# 1_USB_HUB.net
KiCad netlist of a schematic drawn in Altium Designer
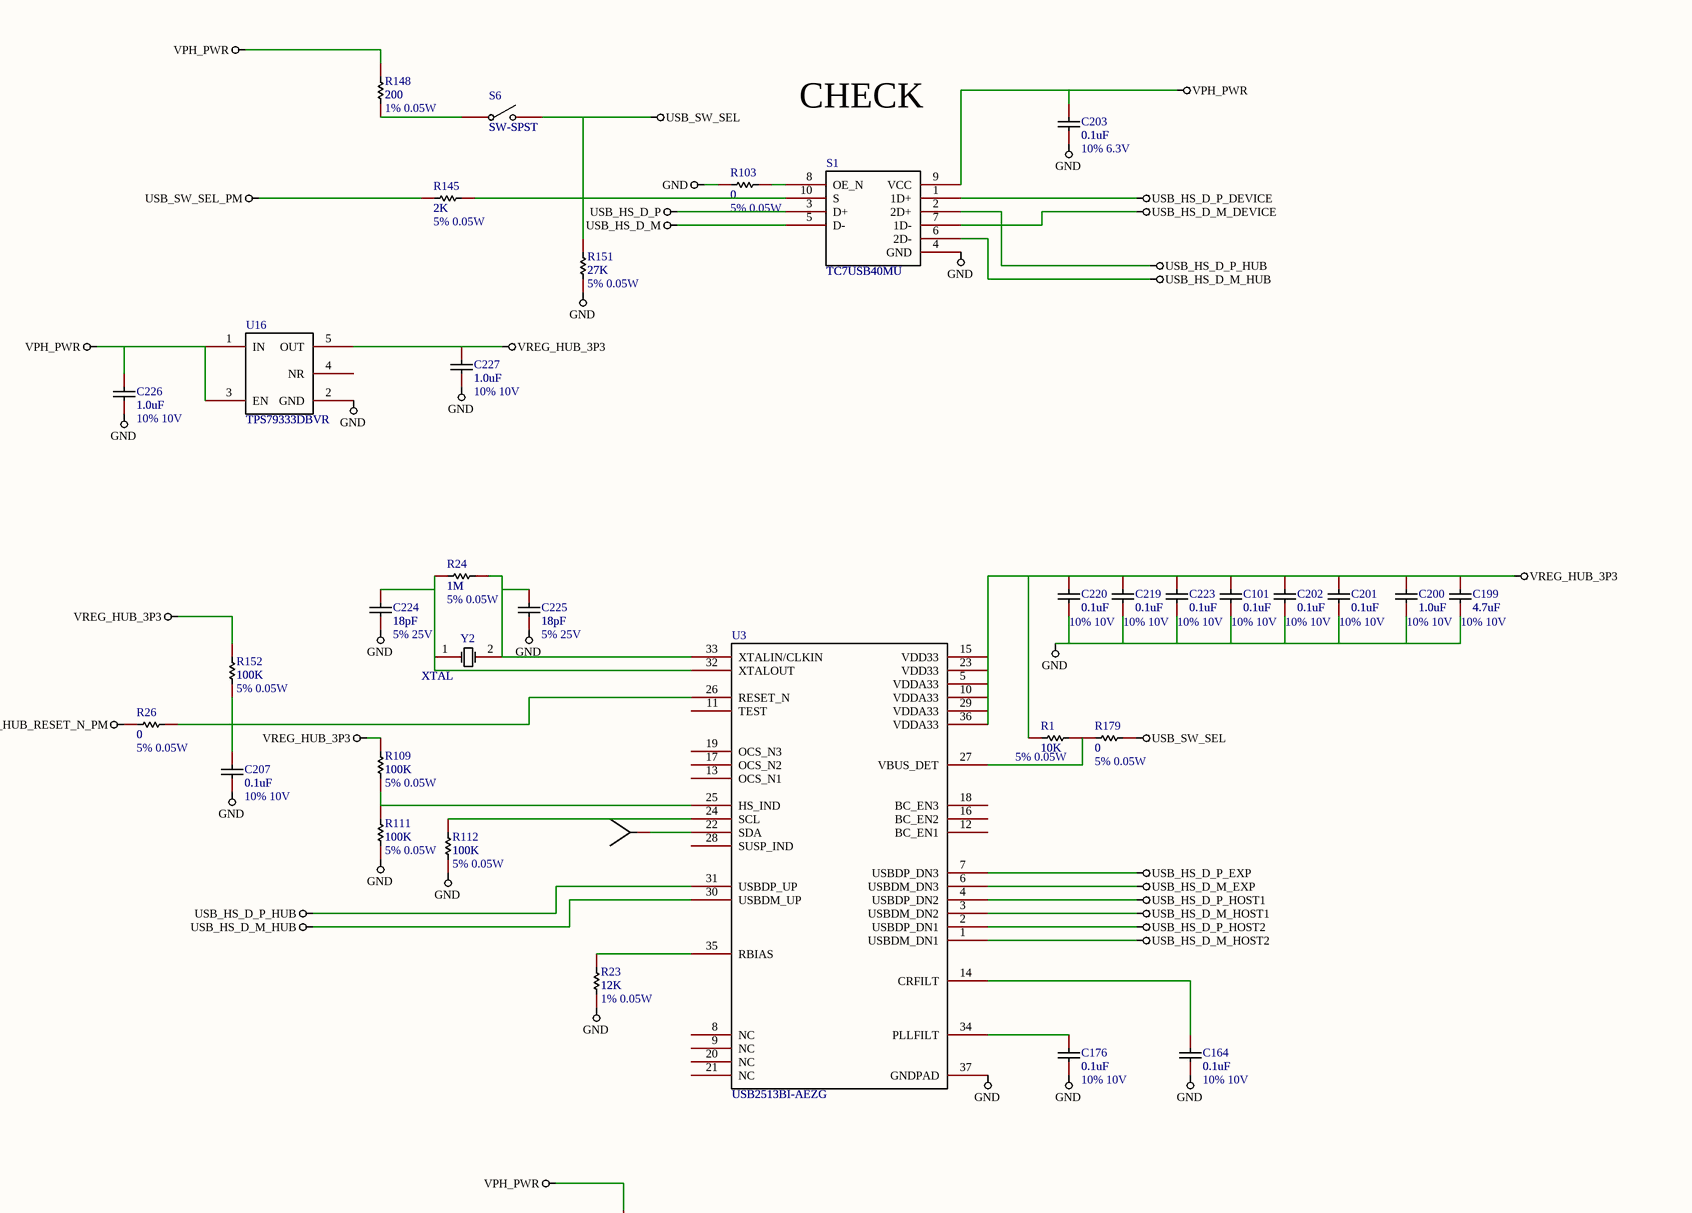
[diagram p0: 1_USB_HUB.schdoc, top left]
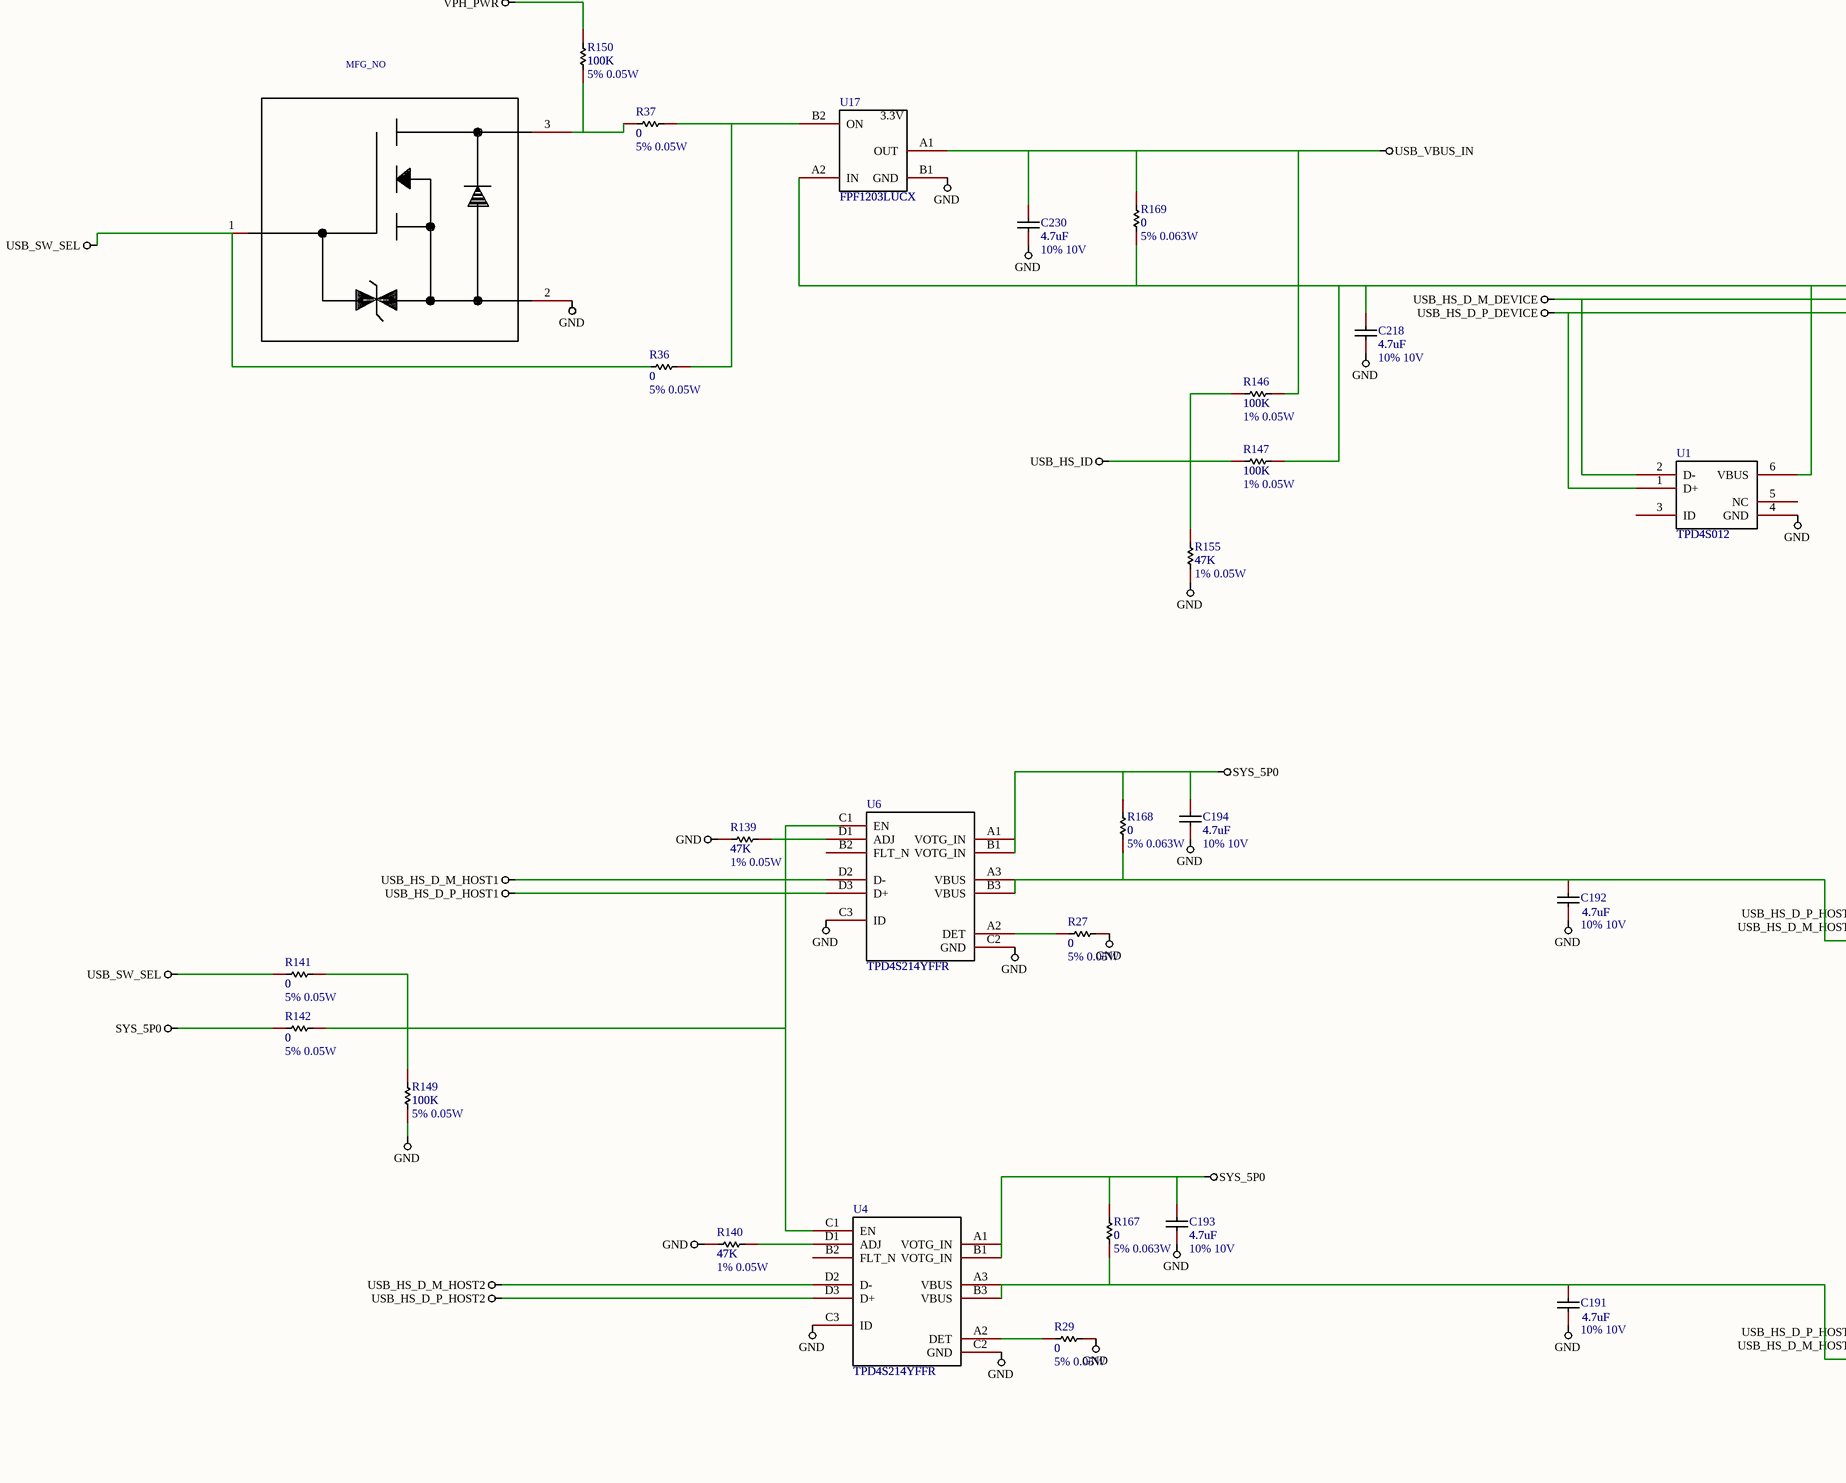
[diagram p1: 1_USB_HUB.schdoc, bottom left]
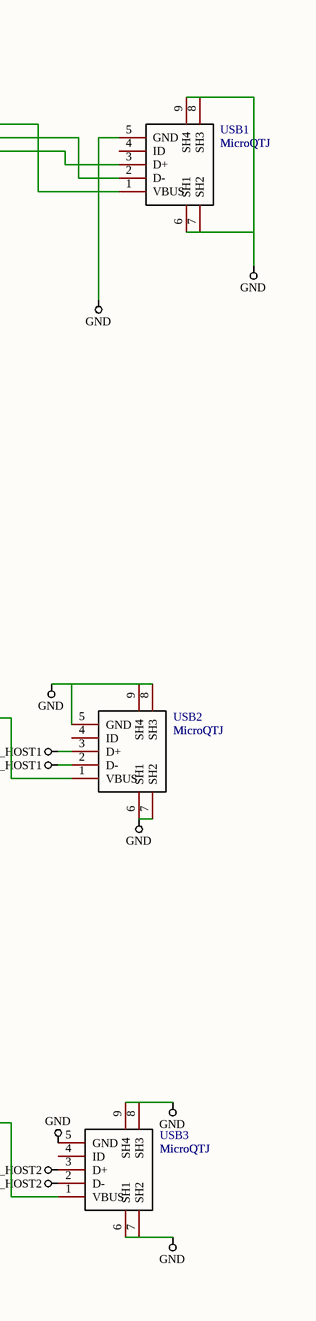
[diagram p2: 1_USB_HUB.schdoc, bottom right]

(export (version "E")
  (design (tool "Eeschema 10.0.6"))
  (components
    (comp (ref "C101")
      (value "0.1uF")
      (description "Capacitor")
      (fields
        (field (name "NAME") "0.1uF")
        (field (name "ALTIUM_VALUE") "10% 10V")
        (field (name "PUBLISHER") "Altium Limited")
      )
      (libsource (lib "altium-import") (part "root_1_0.1uF_"))
    )
    (comp (ref "C164")
      (value "0.1uF")
      (description "Capacitor")
      (fields
        (field (name "NAME") "0.1uF")
        (field (name "ALTIUM_VALUE") "10% 10V")
        (field (name "PUBLISHER") "Altium Limited")
      )
      (libsource (lib "altium-import") (part "root_1_0.1uF_"))
    )
    (comp (ref "C176")
      (value "0.1uF")
      (description "Capacitor")
      (fields
        (field (name "NAME") "0.1uF")
        (field (name "ALTIUM_VALUE") "10% 10V")
        (field (name "PUBLISHER") "Altium Limited")
      )
      (libsource (lib "altium-import") (part "root_1_0.1uF_"))
    )
    (comp (ref "C191")
      (value "4.7uF")
      (description "Capacitor")
      (fields
        (field (name "NAME") "4.7uF")
        (field (name "ALTIUM_VALUE") "10% 10V")
        (field (name "PUBLISHER") "Altium Limited")
      )
      (libsource (lib "altium-import") (part "root_3_4.7uF_"))
    )
    (comp (ref "C192")
      (value "4.7uF")
      (description "Capacitor")
      (fields
        (field (name "NAME") "4.7uF")
        (field (name "ALTIUM_VALUE") "10% 10V")
        (field (name "PUBLISHER") "Altium Limited")
      )
      (libsource (lib "altium-import") (part "root_3_4.7uF_"))
    )
    (comp (ref "C193")
      (value "4.7uF")
      (description "Capacitor")
      (fields
        (field (name "NAME") "4.7uF")
        (field (name "ALTIUM_VALUE") "10% 10V")
        (field (name "PUBLISHER") "Altium Limited")
      )
      (libsource (lib "altium-import") (part "root_1_4.7uF_"))
    )
    (comp (ref "C194")
      (value "4.7uF")
      (description "Capacitor")
      (fields
        (field (name "NAME") "4.7uF")
        (field (name "ALTIUM_VALUE") "10% 10V")
        (field (name "PUBLISHER") "Altium Limited")
      )
      (libsource (lib "altium-import") (part "root_1_4.7uF_"))
    )
    (comp (ref "C199")
      (value "4.7uF")
      (description "Capacitor")
      (fields
        (field (name "NAME") "4.7uF")
        (field (name "ALTIUM_VALUE") "10% 10V")
        (field (name "PUBLISHER") "Altium Limited")
      )
      (libsource (lib "altium-import") (part "root_1_4.7uF_"))
    )
    (comp (ref "C200")
      (value "1.0uF")
      (description "Capacitor")
      (fields
        (field (name "NAME") "1.0uF")
        (field (name "ALTIUM_VALUE") "10% 10V")
        (field (name "PUBLISHER") "Altium Limited")
      )
      (libsource (lib "altium-import") (part "root_1_1.0uF_"))
    )
    (comp (ref "C201")
      (value "0.1uF")
      (description "Capacitor")
      (fields
        (field (name "NAME") "0.1uF")
        (field (name "ALTIUM_VALUE") "10% 10V")
        (field (name "PUBLISHER") "Altium Limited")
      )
      (libsource (lib "altium-import") (part "root_1_0.1uF_"))
    )
    (comp (ref "C202")
      (value "0.1uF")
      (description "Capacitor")
      (fields
        (field (name "NAME") "0.1uF")
        (field (name "ALTIUM_VALUE") "10% 10V")
        (field (name "PUBLISHER") "Altium Limited")
      )
      (libsource (lib "altium-import") (part "root_1_0.1uF_"))
    )
    (comp (ref "C203")
      (value "0.1uF")
      (description "Capacitor")
      (fields
        (field (name "NAME") "0.1uF")
        (field (name "ALTIUM_VALUE") "10% 6.3V")
        (field (name "PUBLISHER") "Altium Limited")
      )
      (libsource (lib "altium-import") (part "root_3_0.1uF_"))
    )
    (comp (ref "C207")
      (value "0.1uF")
      (description "Capacitor")
      (fields
        (field (name "NAME") "0.1uF")
        (field (name "ALTIUM_VALUE") "10% 10V")
        (field (name "PUBLISHER") "Altium Limited")
      )
      (libsource (lib "altium-import") (part "root_1_0.1uF_"))
    )
    (comp (ref "C218")
      (value "4.7uF")
      (description "Capacitor")
      (fields
        (field (name "NAME") "4.7uF")
        (field (name "ALTIUM_VALUE") "10% 10V")
        (field (name "PUBLISHER") "Altium Limited")
      )
      (libsource (lib "altium-import") (part "root_1_4.7uF_"))
    )
    (comp (ref "C219")
      (value "0.1uF")
      (description "Capacitor")
      (fields
        (field (name "NAME") "0.1uF")
        (field (name "ALTIUM_VALUE") "10% 10V")
        (field (name "PUBLISHER") "Altium Limited")
      )
      (libsource (lib "altium-import") (part "root_1_0.1uF_"))
    )
    (comp (ref "C220")
      (value "0.1uF")
      (description "Capacitor")
      (fields
        (field (name "NAME") "0.1uF")
        (field (name "ALTIUM_VALUE") "10% 10V")
        (field (name "PUBLISHER") "Altium Limited")
      )
      (libsource (lib "altium-import") (part "root_1_0.1uF_"))
    )
    (comp (ref "C223")
      (value "0.1uF")
      (description "Capacitor")
      (fields
        (field (name "NAME") "0.1uF")
        (field (name "ALTIUM_VALUE") "10% 10V")
        (field (name "PUBLISHER") "Altium Limited")
      )
      (libsource (lib "altium-import") (part "root_1_0.1uF_"))
    )
    (comp (ref "C224")
      (value "18pF")
      (description "Capacitor")
      (fields
        (field (name "NAME") "18pF")
        (field (name "ALTIUM_VALUE") "5% 25V")
        (field (name "PUBLISHER") "Altium Limited")
      )
      (libsource (lib "altium-import") (part "root_1_18pF_"))
    )
    (comp (ref "C225")
      (value "18pF")
      (description "Capacitor")
      (fields
        (field (name "NAME") "18pF")
        (field (name "ALTIUM_VALUE") "5% 25V")
        (field (name "PUBLISHER") "Altium Limited")
      )
      (libsource (lib "altium-import") (part "root_1_18pF_"))
    )
    (comp (ref "C226")
      (value "1.0uF")
      (description "Capacitor")
      (fields
        (field (name "NAME") "1.0uF")
        (field (name "ALTIUM_VALUE") "10% 10V")
        (field (name "PUBLISHER") "Altium Limited")
      )
      (libsource (lib "altium-import") (part "root_1_1.0uF_"))
    )
    (comp (ref "C227")
      (value "1.0uF")
      (description "Capacitor")
      (fields
        (field (name "NAME") "1.0uF")
        (field (name "ALTIUM_VALUE") "10% 10V")
        (field (name "PUBLISHER") "Altium Limited")
      )
      (libsource (lib "altium-import") (part "root_1_1.0uF_"))
    )
    (comp (ref "C230")
      (value "4.7uF")
      (description "Capacitor")
      (fields
        (field (name "NAME") "4.7uF")
        (field (name "ALTIUM_VALUE") "10% 10V")
        (field (name "PUBLISHER") "Altium Limited")
      )
      (libsource (lib "altium-import") (part "root_1_4.7uF_"))
    )
    (comp (ref "Q1")
      (value "nfet_zener_bidir")
      (fields
        (field (name "PART_NUMBER") "MCN_NO")
        (field (name "PART_ID") "MFG_NO")
        (field (name "LIBRARY NAME") "MSM8916_DRAM_PMIC_REF_Library")
      )
      (libsource (lib "altium-import") (part "root_0_nfet_zener_bidir_"))
    )
    (comp (ref "R1")
      (value "10K")
      (description "Resistor")
      (fields
        (field (name "NAME") "10K")
        (field (name "ALTIUM_VALUE") "5% 0.05W")
        (field (name "PUBLISHER") "Altium Limited")
      )
      (libsource (lib "altium-import") (part "root_2_10K_"))
    )
    (comp (ref "R23")
      (value "12K")
      (description "Resistor")
      (fields
        (field (name "NAME") "12K")
        (field (name "ALTIUM_VALUE") "1% 0.05W")
        (field (name "PUBLISHER") "Altium Limited")
      )
      (libsource (lib "altium-import") (part "root_1_12K_"))
    )
    (comp (ref "R24")
      (value "1M")
      (description "Resistor")
      (fields
        (field (name "NAME") "1M")
        (field (name "ALTIUM_VALUE") "5% 0.05W")
        (field (name "PUBLISHER") "Altium Limited")
      )
      (libsource (lib "altium-import") (part "root_0_1M_"))
    )
    (comp (ref "R26")
      (value "0")
      (description "Resistor")
      (fields
        (field (name "NAME") "0")
        (field (name "ALTIUM_VALUE") "5% 0.05W")
        (field (name "PUBLISHER") "Altium Limited")
      )
      (libsource (lib "altium-import") (part "root_0_0_"))
    )
    (comp (ref "R27")
      (value "0")
      (description "Resistor")
      (fields
        (field (name "NAME") "0")
        (field (name "ALTIUM_VALUE") "5% 0.05W")
        (field (name "PUBLISHER") "Altium Limited")
      )
      (libsource (lib "altium-import") (part "root_0_0_"))
    )
    (comp (ref "R29")
      (value "0")
      (description "Resistor")
      (fields
        (field (name "NAME") "0")
        (field (name "ALTIUM_VALUE") "5% 0.05W")
        (field (name "PUBLISHER") "Altium Limited")
      )
      (libsource (lib "altium-import") (part "root_0_0_"))
    )
    (comp (ref "R36")
      (value "0")
      (description "Resistor")
      (fields
        (field (name "NAME") "0")
        (field (name "ALTIUM_VALUE") "5% 0.05W")
        (field (name "PUBLISHER") "Altium Limited")
      )
      (libsource (lib "altium-import") (part "root_0_0_"))
    )
    (comp (ref "R37")
      (value "0")
      (description "Resistor")
      (fields
        (field (name "NAME") "0")
        (field (name "ALTIUM_VALUE") "5% 0.05W")
        (field (name "PUBLISHER") "Altium Limited")
      )
      (libsource (lib "altium-import") (part "root_0_0_"))
    )
    (comp (ref "R103")
      (value "0")
      (description "Resistor")
      (fields
        (field (name "NAME") "0")
        (field (name "ALTIUM_VALUE") "5% 0.05W")
        (field (name "PUBLISHER") "Altium Limited")
      )
      (libsource (lib "altium-import") (part "root_0_0_"))
    )
    (comp (ref "R109")
      (value "100K")
      (description "Resistor")
      (fields
        (field (name "NAME") "100K")
        (field (name "ALTIUM_VALUE") "5% 0.05W")
        (field (name "PUBLISHER") "Altium Limited")
      )
      (libsource (lib "altium-import") (part "root_1_100K_"))
    )
    (comp (ref "R111")
      (value "100K")
      (description "Resistor")
      (fields
        (field (name "NAME") "100K")
        (field (name "ALTIUM_VALUE") "5% 0.05W")
        (field (name "PUBLISHER") "Altium Limited")
      )
      (libsource (lib "altium-import") (part "root_1_100K_"))
    )
    (comp (ref "R112")
      (value "100K")
      (description "Resistor")
      (fields
        (field (name "NAME") "100K")
        (field (name "ALTIUM_VALUE") "5% 0.05W")
        (field (name "PUBLISHER") "Altium Limited")
      )
      (libsource (lib "altium-import") (part "root_1_100K_"))
    )
    (comp (ref "R139")
      (value "47K")
      (description "Resistor")
      (fields
        (field (name "NAME") "47K")
        (field (name "ALTIUM_VALUE") "1% 0.05W")
        (field (name "PUBLISHER") "Altium Limited")
      )
      (libsource (lib "altium-import") (part "root_0_47K_"))
    )
    (comp (ref "R140")
      (value "47K")
      (description "Resistor")
      (fields
        (field (name "NAME") "47K")
        (field (name "ALTIUM_VALUE") "1% 0.05W")
        (field (name "PUBLISHER") "Altium Limited")
      )
      (libsource (lib "altium-import") (part "root_0_47K_"))
    )
    (comp (ref "R141")
      (value "0")
      (description "Resistor")
      (fields
        (field (name "NAME") "0")
        (field (name "ALTIUM_VALUE") "5% 0.05W")
        (field (name "PUBLISHER") "Altium Limited")
      )
      (libsource (lib "altium-import") (part "root_0_0_"))
    )
    (comp (ref "R142")
      (value "0")
      (description "Resistor")
      (fields
        (field (name "NAME") "0")
        (field (name "ALTIUM_VALUE") "5% 0.05W")
        (field (name "PUBLISHER") "Altium Limited")
      )
      (libsource (lib "altium-import") (part "root_0_0_"))
    )
    (comp (ref "R145")
      (value "2K")
      (description "Resistor")
      (fields
        (field (name "NAME") "2K")
        (field (name "ALTIUM_VALUE") "5% 0.05W")
        (field (name "PUBLISHER") "Altium Limited")
      )
      (libsource (lib "altium-import") (part "root_0_2K_"))
    )
    (comp (ref "R146")
      (value "100K")
      (description "Resistor")
      (fields
        (field (name "NAME") "100K")
        (field (name "ALTIUM_VALUE") "1% 0.05W")
        (field (name "PUBLISHER") "Altium Limited")
      )
      (libsource (lib "altium-import") (part "root_0_100K_"))
    )
    (comp (ref "R147")
      (value "100K")
      (description "Resistor")
      (fields
        (field (name "NAME") "100K")
        (field (name "ALTIUM_VALUE") "1% 0.05W")
        (field (name "PUBLISHER") "Altium Limited")
      )
      (libsource (lib "altium-import") (part "root_0_100K_"))
    )
    (comp (ref "R148")
      (value "200")
      (description "Resistor")
      (fields
        (field (name "NAME") "200")
        (field (name "ALTIUM_VALUE") "1% 0.05W")
        (field (name "PUBLISHER") "Altium Limited")
      )
      (libsource (lib "altium-import") (part "root_1_200_"))
    )
    (comp (ref "R149")
      (value "100K")
      (description "Resistor")
      (fields
        (field (name "NAME") "100K")
        (field (name "ALTIUM_VALUE") "5% 0.05W")
        (field (name "PUBLISHER") "Altium Limited")
      )
      (libsource (lib "altium-import") (part "root_1_100K_"))
    )
    (comp (ref "R150")
      (value "100K")
      (description "Resistor")
      (fields
        (field (name "NAME") "100K")
        (field (name "ALTIUM_VALUE") "5% 0.05W")
        (field (name "PUBLISHER") "Altium Limited")
      )
      (libsource (lib "altium-import") (part "root_1_100K_"))
    )
    (comp (ref "R151")
      (value "27K")
      (description "Resistor")
      (fields
        (field (name "NAME") "27K")
        (field (name "ALTIUM_VALUE") "5% 0.05W")
        (field (name "PUBLISHER") "Altium Limited")
      )
      (libsource (lib "altium-import") (part "root_1_27K_"))
    )
    (comp (ref "R152")
      (value "100K")
      (description "Resistor")
      (fields
        (field (name "NAME") "100K")
        (field (name "ALTIUM_VALUE") "5% 0.05W")
        (field (name "PUBLISHER") "Altium Limited")
      )
      (libsource (lib "altium-import") (part "root_1_100K_"))
    )
    (comp (ref "R155")
      (value "47K")
      (description "Resistor")
      (fields
        (field (name "NAME") "47K")
        (field (name "ALTIUM_VALUE") "1% 0.05W")
        (field (name "PUBLISHER") "Altium Limited")
      )
      (libsource (lib "altium-import") (part "root_1_47K_"))
    )
    (comp (ref "R167")
      (value "0")
      (description "Resistor")
      (fields
        (field (name "NAME") "0")
        (field (name "ALTIUM_VALUE") "5% 0.063W")
        (field (name "PUBLISHER") "Altium Limited")
      )
      (libsource (lib "altium-import") (part "root_1_0_"))
    )
    (comp (ref "R168")
      (value "0")
      (description "Resistor")
      (fields
        (field (name "NAME") "0")
        (field (name "ALTIUM_VALUE") "5% 0.063W")
        (field (name "PUBLISHER") "Altium Limited")
      )
      (libsource (lib "altium-import") (part "root_1_0_"))
    )
    (comp (ref "R169")
      (value "0")
      (description "Resistor")
      (fields
        (field (name "NAME") "0")
        (field (name "ALTIUM_VALUE") "5% 0.063W")
        (field (name "PUBLISHER") "Altium Limited")
      )
      (libsource (lib "altium-import") (part "root_1_0_"))
    )
    (comp (ref "R179")
      (value "0")
      (description "Resistor")
      (fields
        (field (name "NAME") "0")
        (field (name "ALTIUM_VALUE") "5% 0.05W")
        (field (name "PUBLISHER") "Altium Limited")
      )
      (libsource (lib "altium-import") (part "root_2_0_"))
    )
    (comp (ref "S1")
      (value "TC7USB40MU")
      (fields
        (field (name "NAME") "TC7USB40MU")
        (field (name "LIBRARY NAME") "MSM8916_DRAM_PMIC_REF_Library")
      )
      (libsource (lib "altium-import") (part "root_0_TC7USB40MU_"))
    )
    (comp (ref "S6")
      (value "SW-SPST")
      (description "Single-Pole, Single-Throw Switch")
      (fields (field (name "NAME") "SW-SPST") (field (name "PUBLISHER") "Altium Limited"))
      (libsource (lib "altium-import") (part "root_0_SW-SPST_"))
    )
    (comp (ref "TP18")
      (value "TP")
      (fields
        (field (name "PART_NUMBER") "MCN_NO")
        (field (name "LIBRARY NAME") "MSM8916_DRAM_PMIC_REF_Library")
      )
      (libsource (lib "altium-import") (part "root_1_TP_"))
    )
    (comp (ref "U1")
      (value "TPD4S012")
      (fields (field (name "NAME") "TPD4S012") (field (name "LIBRARY NAME") "MSM8916_DRAM_PMIC_REF_Library"))
      (libsource (lib "altium-import") (part "root_0_TPD4S012_"))
    )
    (comp (ref "U3")
      (value "USB2513BI-AEZG")
      (fields
        (field (name "NAME") "USB2513BI-AEZG")
        (field (name "LIBRARY NAME") "MSM8916_DRAM_PMIC_REF_Library")
      )
      (libsource (lib "altium-import") (part "root_0_USB2513BI-AEZG_"))
    )
    (comp (ref "U4")
      (value "TPD4S214YFFR")
      (fields
        (field (name "NAME") "TPD4S214YFFR")
        (field (name "LIBRARY NAME") "MSM8916_DRAM_PMIC_REF_Library")
      )
      (libsource (lib "altium-import") (part "root_0_TPD4S214YFFR_"))
    )
    (comp (ref "U6")
      (value "TPD4S214YFFR")
      (fields
        (field (name "NAME") "TPD4S214YFFR")
        (field (name "LIBRARY NAME") "MSM8916_DRAM_PMIC_REF_Library")
      )
      (libsource (lib "altium-import") (part "root_0_TPD4S214YFFR_"))
    )
    (comp (ref "U16")
      (value "TPS79333DBVR")
      (fields
        (field (name "NAME") "TPS79333DBVR")
        (field (name "LIBRARY NAME") "MSM8916_DRAM_PMIC_REF_Library")
      )
      (libsource (lib "altium-import") (part "root_0_TPS79333DBVR_"))
    )
    (comp (ref "U17")
      (value "FPF1203LUCX")
      (fields
        (field (name "NAME") "FPF1203LUCX")
        (field (name "LIBRARY NAME") "MSM8916_DRAM_PMIC_REF_Library")
      )
      (libsource (lib "altium-import") (part "root_0_FPF1203LUCX_"))
    )
    (comp (ref "USB1")
      (value "MicroQTJ")
      (description "连接器类型:Micro-B;标准:USB 2.0;公母:母座;触点数量:5;端口数量:1;安装方式:卧贴;额定电流 - 电源:-;工作温度范围:-30℃~+80℃;")
      (fields (field (name "NAME") "MicroQTJ") (field (name "MANUFACTURER") "SHOU HAN(首韩)"))
      (libsource (lib "altium-import") (part "root_2_MicroQTJ_"))
    )
    (comp (ref "USB2")
      (value "MicroQTJ")
      (description "连接器类型:Micro-B;标准:USB 2.0;公母:母座;触点数量:5;端口数量:1;安装方式:卧贴;额定电流 - 电源:-;工作温度范围:-30℃~+80℃;")
      (fields (field (name "NAME") "MicroQTJ") (field (name "MANUFACTURER") "SHOU HAN(首韩)"))
      (libsource (lib "altium-import") (part "root_2_MicroQTJ_"))
    )
    (comp (ref "USB3")
      (value "MicroQTJ")
      (description "连接器类型:Micro-B;标准:USB 2.0;公母:母座;触点数量:5;端口数量:1;安装方式:卧贴;额定电流 - 电源:-;工作温度范围:-30℃~+80℃;")
      (fields (field (name "NAME") "MicroQTJ") (field (name "MANUFACTURER") "SHOU HAN(首韩)"))
      (libsource (lib "altium-import") (part "root_2_MicroQTJ_"))
    )
    (comp (ref "Y2")
      (value "XTAL")
      (description "Crystal Oscillator")
      (fields (field (name "NAME") "XTAL") (field (name "PUBLISHER") "Altium Limited"))
      (libsource (lib "altium-import") (part "root_0_XTAL_"))
    )
  )
  (nets
    (net (code "1") (name "GND") (class "Default")
      (node (ref "C101") (pin "1") (pinfunction "1_1") (pintype "passive"))
      (node (ref "C164") (pin "1") (pinfunction "1_1") (pintype "passive"))
      (node (ref "C176") (pin "1") (pinfunction "1_1") (pintype "passive"))
      (node (ref "C191") (pin "2") (pinfunction "2_2") (pintype "passive"))
      (node (ref "C192") (pin "2") (pinfunction "2_2") (pintype "passive"))
      (node (ref "C193") (pin "1") (pinfunction "1_1") (pintype "passive"))
      (node (ref "C194") (pin "1") (pinfunction "1_1") (pintype "passive"))
      (node (ref "C199") (pin "1") (pinfunction "1_1") (pintype "passive"))
      (node (ref "C200") (pin "1") (pinfunction "1_1") (pintype "passive"))
      (node (ref "C201") (pin "1") (pinfunction "1_1") (pintype "passive"))
      (node (ref "C202") (pin "1") (pinfunction "1_1") (pintype "passive"))
      (node (ref "C203") (pin "2") (pinfunction "2_2") (pintype "passive"))
      (node (ref "C207") (pin "1") (pinfunction "1_1") (pintype "passive"))
      (node (ref "C218") (pin "1") (pinfunction "1_1") (pintype "passive"))
      (node (ref "C219") (pin "1") (pinfunction "1_1") (pintype "passive"))
      (node (ref "C220") (pin "1") (pinfunction "1_1") (pintype "passive"))
      (node (ref "C223") (pin "1") (pinfunction "1_1") (pintype "passive"))
      (node (ref "C224") (pin "1") (pinfunction "1_1") (pintype "passive"))
      (node (ref "C225") (pin "1") (pinfunction "1_1") (pintype "passive"))
      (node (ref "C226") (pin "1") (pinfunction "1_1") (pintype "passive"))
      (node (ref "C227") (pin "1") (pinfunction "1_1") (pintype "passive"))
      (node (ref "C230") (pin "1") (pinfunction "1_1") (pintype "passive"))
      (node (ref "Q1") (pin "2") (pinfunction "S_2") (pintype "passive"))
      (node (ref "R103") (pin "1") (pinfunction "1_1") (pintype "passive"))
      (node (ref "R111") (pin "1") (pinfunction "1_1") (pintype "passive"))
      (node (ref "R112") (pin "1") (pinfunction "1_1") (pintype "passive"))
      (node (ref "R139") (pin "1") (pinfunction "1_1") (pintype "passive"))
      (node (ref "R140") (pin "1") (pinfunction "1_1") (pintype "passive"))
      (node (ref "R149") (pin "1") (pinfunction "1_1") (pintype "passive"))
      (node (ref "R151") (pin "1") (pinfunction "1_1") (pintype "passive"))
      (node (ref "R155") (pin "1") (pinfunction "1_1") (pintype "passive"))
      (node (ref "R23") (pin "1") (pinfunction "1_1") (pintype "passive"))
      (node (ref "R27") (pin "2") (pinfunction "2_2") (pintype "passive"))
      (node (ref "R29") (pin "2") (pinfunction "2_2") (pintype "passive"))
      (node (ref "S1") (pin "4") (pinfunction "GND_4") (pintype "passive"))
      (node (ref "U1") (pin "4") (pinfunction "GND_4") (pintype "passive"))
      (node (ref "U16") (pin "2") (pinfunction "GND_2") (pintype "passive"))
      (node (ref "U17") (pin "B1") (pinfunction "GND_B1") (pintype "passive"))
      (node (ref "U3") (pin "37") (pinfunction "GNDPAD_37") (pintype "passive"))
      (node (ref "U4") (pin "C2") (pinfunction "GND_C2") (pintype "passive"))
      (node (ref "U4") (pin "C3") (pinfunction "ID_C3") (pintype "passive"))
      (node (ref "U6") (pin "C2") (pinfunction "GND_C2") (pintype "passive"))
      (node (ref "U6") (pin "C3") (pinfunction "ID_C3") (pintype "passive"))
      (node (ref "USB1") (pin "5") (pinfunction "GND_5") (pintype "passive"))
      (node (ref "USB1") (pin "6") (pinfunction "SH1_6") (pintype "passive"))
      (node (ref "USB1") (pin "7") (pinfunction "SH2_7") (pintype "passive"))
      (node (ref "USB1") (pin "8") (pinfunction "SH3_8") (pintype "passive"))
      (node (ref "USB1") (pin "9") (pinfunction "SH4_9") (pintype "passive"))
      (node (ref "USB2") (pin "5") (pinfunction "GND_5") (pintype "passive"))
      (node (ref "USB2") (pin "6") (pinfunction "SH1_6") (pintype "passive"))
      (node (ref "USB2") (pin "7") (pinfunction "SH2_7") (pintype "passive"))
      (node (ref "USB2") (pin "8") (pinfunction "SH3_8") (pintype "passive"))
      (node (ref "USB2") (pin "9") (pinfunction "SH4_9") (pintype "passive"))
      (node (ref "USB3") (pin "5") (pinfunction "GND_5") (pintype "passive"))
      (node (ref "USB3") (pin "6") (pinfunction "SH1_6") (pintype "passive"))
      (node (ref "USB3") (pin "7") (pinfunction "SH2_7") (pintype "passive"))
      (node (ref "USB3") (pin "8") (pinfunction "SH3_8") (pintype "passive"))
      (node (ref "USB3") (pin "9") (pinfunction "SH4_9") (pintype "passive"))
    )
    (net (code "2") (name "Net-(Q1-D)") (class "Default")
      (node (ref "Q1") (pin "3") (pinfunction "D_3") (pintype "passive"))
      (node (ref "R150") (pin "1") (pinfunction "1_1") (pintype "passive"))
      (node (ref "R37") (pin "1") (pinfunction "1_1") (pintype "passive"))
    )
    (net (code "3") (name "Net-(S1-OE_N)") (class "Default")
      (node (ref "R103") (pin "2") (pinfunction "2_2") (pintype "passive"))
      (node (ref "S1") (pin "8") (pinfunction "OE_N_8") (pintype "passive"))
    )
    (net (code "4") (name "Net-(S6-COMMON)") (class "Default")
      (node (ref "R148") (pin "1") (pinfunction "1_1") (pintype "passive"))
      (node (ref "S6") (pin "1") (pinfunction "COMMON_1") (pintype "passive"))
    )
    (net (code "5") (name "Net-(TP18-IO1)") (class "Default")
      (node (ref "TP18") (pin "1") (pinfunction "IO1_1") (pintype "passive"))
      (node (ref "U3") (pin "22") (pinfunction "SDA_22") (pintype "passive"))
    )
    (net (code "6") (name "Net-(U1-VBUS)") (class "Default")
      (node (ref "C218") (pin "2") (pinfunction "2_2") (pintype "passive"))
      (node (ref "R147") (pin "2") (pinfunction "2_2") (pintype "passive"))
      (node (ref "R169") (pin "1") (pinfunction "1_1") (pintype "passive"))
      (node (ref "U1") (pin "6") (pinfunction "VBUS_6") (pintype "passive"))
      (node (ref "U17") (pin "A2") (pinfunction "IN_A2") (pintype "passive"))
      (node (ref "USB1") (pin "1") (pinfunction "VBUS_1") (pintype "passive"))
    )
    (net (code "7") (name "Net-(U3-CRFILT)") (class "Default")
      (node (ref "C164") (pin "2") (pinfunction "2_2") (pintype "passive"))
      (node (ref "U3") (pin "14") (pinfunction "CRFILT_14") (pintype "passive"))
    )
    (net (code "8") (name "Net-(U3-HS_IND)") (class "Default")
      (node (ref "R109") (pin "1") (pinfunction "1_1") (pintype "passive"))
      (node (ref "R111") (pin "2") (pinfunction "2_2") (pintype "passive"))
      (node (ref "U3") (pin "25") (pinfunction "HS_IND_25") (pintype "passive"))
    )
    (net (code "9") (name "Net-(U3-PLLFILT)") (class "Default")
      (node (ref "C176") (pin "2") (pinfunction "2_2") (pintype "passive"))
      (node (ref "U3") (pin "34") (pinfunction "PLLFILT_34") (pintype "passive"))
    )
    (net (code "10") (name "Net-(U3-RBIAS)") (class "Default")
      (node (ref "R23") (pin "2") (pinfunction "2_2") (pintype "passive"))
      (node (ref "U3") (pin "35") (pinfunction "RBIAS_35") (pintype "passive"))
    )
    (net (code "11") (name "Net-(U3-RESET_N)") (class "Default")
      (node (ref "C207") (pin "2") (pinfunction "2_2") (pintype "passive"))
      (node (ref "R152") (pin "1") (pinfunction "1_1") (pintype "passive"))
      (node (ref "R26") (pin "2") (pinfunction "2_2") (pintype "passive"))
      (node (ref "U3") (pin "26") (pinfunction "RESET_N_26") (pintype "passive"))
    )
    (net (code "12") (name "Net-(U3-SCL)") (class "Default")
      (node (ref "R112") (pin "2") (pinfunction "2_2") (pintype "passive"))
      (node (ref "U3") (pin "24") (pinfunction "SCL_24") (pintype "passive"))
    )
    (net (code "13") (name "Net-(U3-VBUS_DET)") (class "Default")
      (node (ref "R1") (pin "1") (pinfunction "1_1") (pintype "passive"))
      (node (ref "R179") (pin "2") (pinfunction "2_2") (pintype "passive"))
      (node (ref "U3") (pin "27") (pinfunction "VBUS_DET_27") (pintype "passive"))
    )
    (net (code "14") (name "Net-(U3-XTALIN{slash}CLKIN)") (class "Default")
      (node (ref "C225") (pin "2") (pinfunction "2_2") (pintype "passive"))
      (node (ref "R24") (pin "2") (pinfunction "2_2") (pintype "passive"))
      (node (ref "U3") (pin "33") (pinfunction "XTALIN/CLKIN_33") (pintype "passive"))
      (node (ref "Y2") (pin "2") (pinfunction "OSC2_2") (pintype "passive"))
    )
    (net (code "15") (name "Net-(U3-XTALOUT)") (class "Default")
      (node (ref "C224") (pin "2") (pinfunction "2_2") (pintype "passive"))
      (node (ref "R24") (pin "1") (pinfunction "1_1") (pintype "passive"))
      (node (ref "U3") (pin "32") (pinfunction "XTALOUT_32") (pintype "passive"))
      (node (ref "Y2") (pin "1") (pinfunction "OSC1_1") (pintype "passive"))
    )
    (net (code "16") (name "Net-(U4-ADJ)") (class "Default")
      (node (ref "R140") (pin "2") (pinfunction "2_2") (pintype "passive"))
      (node (ref "U4") (pin "D1") (pinfunction "ADJ_D1") (pintype "passive"))
    )
    (net (code "17") (name "Net-(U4-DET)") (class "Default")
      (node (ref "R29") (pin "1") (pinfunction "1_1") (pintype "passive"))
      (node (ref "U4") (pin "A2") (pinfunction "DET_A2") (pintype "passive"))
    )
    (net (code "18") (name "Net-(U4-EN)") (class "Default")
      (node (ref "R141") (pin "2") (pinfunction "2_2") (pintype "passive"))
      (node (ref "R142") (pin "2") (pinfunction "2_2") (pintype "passive"))
      (node (ref "R149") (pin "2") (pinfunction "2_2") (pintype "passive"))
      (node (ref "U4") (pin "C1") (pinfunction "EN_C1") (pintype "passive"))
      (node (ref "U6") (pin "C1") (pinfunction "EN_C1") (pintype "passive"))
    )
    (net (code "19") (name "Net-(U6-ADJ)") (class "Default")
      (node (ref "R139") (pin "2") (pinfunction "2_2") (pintype "passive"))
      (node (ref "U6") (pin "D1") (pinfunction "ADJ_D1") (pintype "passive"))
    )
    (net (code "20") (name "Net-(U6-DET)") (class "Default")
      (node (ref "R27") (pin "1") (pinfunction "1_1") (pintype "passive"))
      (node (ref "U6") (pin "A2") (pinfunction "DET_A2") (pintype "passive"))
    )
    (net (code "21") (name "Net-(U17-ON)") (class "Default")
      (node (ref "R36") (pin "2") (pinfunction "2_2") (pintype "passive"))
      (node (ref "R37") (pin "2") (pinfunction "2_2") (pintype "passive"))
      (node (ref "U17") (pin "B2") (pinfunction "ON_B2") (pintype "passive"))
    )
    (net (code "22") (name "Net-(USB2-VBUS)") (class "Default")
      (node (ref "C192") (pin "1") (pinfunction "1_1") (pintype "passive"))
      (node (ref "R168") (pin "1") (pinfunction "1_1") (pintype "passive"))
      (node (ref "U6") (pin "A3") (pinfunction "VBUS_A3") (pintype "passive"))
      (node (ref "U6") (pin "B3") (pinfunction "VBUS_B3") (pintype "passive"))
      (node (ref "USB2") (pin "1") (pinfunction "VBUS_1") (pintype "passive"))
    )
    (net (code "23") (name "Net-(USB3-VBUS)") (class "Default")
      (node (ref "C191") (pin "1") (pinfunction "1_1") (pintype "passive"))
      (node (ref "R167") (pin "1") (pinfunction "1_1") (pintype "passive"))
      (node (ref "U4") (pin "A3") (pinfunction "VBUS_A3") (pintype "passive"))
      (node (ref "U4") (pin "B3") (pinfunction "VBUS_B3") (pintype "passive"))
      (node (ref "USB3") (pin "1") (pinfunction "VBUS_1") (pintype "passive"))
    )
    (net (code "24") (name "SYS_5P0") (class "Default")
      (node (ref "C193") (pin "2") (pinfunction "2_2") (pintype "passive"))
      (node (ref "C194") (pin "2") (pinfunction "2_2") (pintype "passive"))
      (node (ref "R142") (pin "1") (pinfunction "1_1") (pintype "passive"))
      (node (ref "R167") (pin "2") (pinfunction "2_2") (pintype "passive"))
      (node (ref "R168") (pin "2") (pinfunction "2_2") (pintype "passive"))
      (node (ref "U4") (pin "A1") (pinfunction "VOTG_IN_A1") (pintype "passive"))
      (node (ref "U4") (pin "B1") (pinfunction "VOTG_IN_B1") (pintype "passive"))
      (node (ref "U6") (pin "A1") (pinfunction "VOTG_IN_A1") (pintype "passive"))
      (node (ref "U6") (pin "B1") (pinfunction "VOTG_IN_B1") (pintype "passive"))
    )
    (net (code "25") (name "USB_HS_D_M") (class "Default")
      (node (ref "S1") (pin "5") (pinfunction "D-_5") (pintype "passive"))
    )
    (net (code "26") (name "USB_HS_D_M_DEVICE") (class "Default")
      (node (ref "S1") (pin "7") (pinfunction "1D-_7") (pintype "passive"))
      (node (ref "U1") (pin "2") (pinfunction "D-_2") (pintype "passive"))
      (node (ref "USB1") (pin "2") (pinfunction "D-_2") (pintype "passive"))
    )
    (net (code "27") (name "USB_HS_D_M_EXP") (class "Default")
      (node (ref "U3") (pin "6") (pinfunction "USBDM_DN3_6") (pintype "passive"))
    )
    (net (code "28") (name "USB_HS_D_M_HOST1") (class "Default")
      (node (ref "U3") (pin "3") (pinfunction "USBDM_DN2_3") (pintype "passive"))
      (node (ref "U6") (pin "D2") (pinfunction "D-_D2") (pintype "passive"))
      (node (ref "USB2") (pin "2") (pinfunction "D-_2") (pintype "passive"))
    )
    (net (code "29") (name "USB_HS_D_M_HOST2") (class "Default")
      (node (ref "U3") (pin "1") (pinfunction "USBDM_DN1_1") (pintype "passive"))
      (node (ref "U4") (pin "D2") (pinfunction "D-_D2") (pintype "passive"))
      (node (ref "USB3") (pin "2") (pinfunction "D-_2") (pintype "passive"))
    )
    (net (code "30") (name "USB_HS_D_M_HUB") (class "Default")
      (node (ref "S1") (pin "6") (pinfunction "2D-_6") (pintype "passive"))
      (node (ref "U3") (pin "30") (pinfunction "USBDM_UP_30") (pintype "passive"))
    )
    (net (code "31") (name "USB_HS_D_P") (class "Default")
      (node (ref "S1") (pin "3") (pinfunction "D+_3") (pintype "passive"))
    )
    (net (code "32") (name "USB_HS_D_P_DEVICE") (class "Default")
      (node (ref "S1") (pin "1") (pinfunction "1D+_1") (pintype "passive"))
      (node (ref "U1") (pin "1") (pinfunction "D+_1") (pintype "passive"))
      (node (ref "USB1") (pin "3") (pinfunction "D+_3") (pintype "passive"))
    )
    (net (code "33") (name "USB_HS_D_P_EXP") (class "Default")
      (node (ref "U3") (pin "7") (pinfunction "USBDP_DN3_7") (pintype "passive"))
    )
    (net (code "34") (name "USB_HS_D_P_HOST1") (class "Default")
      (node (ref "U3") (pin "4") (pinfunction "USBDP_DN2_4") (pintype "passive"))
      (node (ref "U6") (pin "D3") (pinfunction "D+_D3") (pintype "passive"))
      (node (ref "USB2") (pin "3") (pinfunction "D+_3") (pintype "passive"))
    )
    (net (code "35") (name "USB_HS_D_P_HOST2") (class "Default")
      (node (ref "U3") (pin "2") (pinfunction "USBDP_DN1_2") (pintype "passive"))
      (node (ref "U4") (pin "D3") (pinfunction "D+_D3") (pintype "passive"))
      (node (ref "USB3") (pin "3") (pinfunction "D+_3") (pintype "passive"))
    )
    (net (code "36") (name "USB_HS_D_P_HUB") (class "Default")
      (node (ref "S1") (pin "2") (pinfunction "2D+_2") (pintype "passive"))
      (node (ref "U3") (pin "31") (pinfunction "USBDP_UP_31") (pintype "passive"))
    )
    (net (code "37") (name "USB_HS_ID") (class "Default")
      (node (ref "R146") (pin "1") (pinfunction "1_1") (pintype "passive"))
      (node (ref "R147") (pin "1") (pinfunction "1_1") (pintype "passive"))
      (node (ref "R155") (pin "2") (pinfunction "2_2") (pintype "passive"))
    )
    (net (code "38") (name "USB_HUB_RESET_N_PM") (class "Default")
      (node (ref "R26") (pin "1") (pinfunction "1_1") (pintype "passive"))
    )
    (net (code "39") (name "USB_SW_SEL") (class "Default")
      (node (ref "Q1") (pin "1") (pinfunction "G_1") (pintype "passive"))
      (node (ref "R141") (pin "1") (pinfunction "1_1") (pintype "passive"))
      (node (ref "R145") (pin "2") (pinfunction "2_2") (pintype "passive"))
      (node (ref "R151") (pin "2") (pinfunction "2_2") (pintype "passive"))
      (node (ref "R179") (pin "1") (pinfunction "1_1") (pintype "passive"))
      (node (ref "R36") (pin "1") (pinfunction "1_1") (pintype "passive"))
      (node (ref "S1") (pin "10") (pinfunction "S_10") (pintype "passive"))
      (node (ref "S6") (pin "2") (pinfunction "NO_2") (pintype "passive"))
    )
    (net (code "40") (name "USB_SW_SEL_PM") (class "Default")
      (node (ref "R145") (pin "1") (pinfunction "1_1") (pintype "passive"))
    )
    (net (code "41") (name "USB_VBUS_IN") (class "Default")
      (node (ref "C230") (pin "2") (pinfunction "2_2") (pintype "passive"))
      (node (ref "R146") (pin "2") (pinfunction "2_2") (pintype "passive"))
      (node (ref "R169") (pin "2") (pinfunction "2_2") (pintype "passive"))
      (node (ref "U17") (pin "A1") (pinfunction "OUT_A1") (pintype "passive"))
    )
    (net (code "42") (name "VPH_PWR") (class "Default")
      (node (ref "C203") (pin "1") (pinfunction "1_1") (pintype "passive"))
      (node (ref "C226") (pin "2") (pinfunction "2_2") (pintype "passive"))
      (node (ref "R148") (pin "2") (pinfunction "2_2") (pintype "passive"))
      (node (ref "R150") (pin "2") (pinfunction "2_2") (pintype "passive"))
      (node (ref "S1") (pin "9") (pinfunction "VCC_9") (pintype "passive"))
      (node (ref "U16") (pin "1") (pinfunction "IN_1") (pintype "passive"))
      (node (ref "U16") (pin "3") (pinfunction "EN_3") (pintype "passive"))
    )
    (net (code "43") (name "VREG_HUB_3P3") (class "Default")
      (node (ref "C101") (pin "2") (pinfunction "2_2") (pintype "passive"))
      (node (ref "C199") (pin "2") (pinfunction "2_2") (pintype "passive"))
      (node (ref "C200") (pin "2") (pinfunction "2_2") (pintype "passive"))
      (node (ref "C201") (pin "2") (pinfunction "2_2") (pintype "passive"))
      (node (ref "C202") (pin "2") (pinfunction "2_2") (pintype "passive"))
      (node (ref "C219") (pin "2") (pinfunction "2_2") (pintype "passive"))
      (node (ref "C220") (pin "2") (pinfunction "2_2") (pintype "passive"))
      (node (ref "C223") (pin "2") (pinfunction "2_2") (pintype "passive"))
      (node (ref "C227") (pin "2") (pinfunction "2_2") (pintype "passive"))
      (node (ref "R1") (pin "2") (pinfunction "2_2") (pintype "passive"))
      (node (ref "R109") (pin "2") (pinfunction "2_2") (pintype "passive"))
      (node (ref "R152") (pin "2") (pinfunction "2_2") (pintype "passive"))
      (node (ref "U16") (pin "5") (pinfunction "OUT_5") (pintype "passive"))
      (node (ref "U3") (pin "10") (pinfunction "VDDA33_10") (pintype "passive"))
      (node (ref "U3") (pin "15") (pinfunction "VDD33_15") (pintype "passive"))
      (node (ref "U3") (pin "23") (pinfunction "VDD33_23") (pintype "passive"))
      (node (ref "U3") (pin "29") (pinfunction "VDDA33_29") (pintype "passive"))
      (node (ref "U3") (pin "36") (pinfunction "VDDA33_36") (pintype "passive"))
      (node (ref "U3") (pin "5") (pinfunction "VDDA33_5") (pintype "passive"))
    )
    (net (code "44") (name "unconnected-(U1-ID-Pad3)") (class "Default")
      (node (ref "U1") (pin "3") (pinfunction "ID_3") (pintype "passive"))
    )
    (net (code "45") (name "unconnected-(U1-NC-Pad5)") (class "Default")
      (node (ref "U1") (pin "5") (pinfunction "NC_5") (pintype "passive"))
    )
    (net (code "46") (name "unconnected-(U3-BC_EN1-Pad12)") (class "Default")
      (node (ref "U3") (pin "12") (pinfunction "BC_EN1_12") (pintype "passive"))
    )
    (net (code "47") (name "unconnected-(U3-BC_EN2-Pad16)") (class "Default")
      (node (ref "U3") (pin "16") (pinfunction "BC_EN2_16") (pintype "passive"))
    )
    (net (code "48") (name "unconnected-(U3-BC_EN3-Pad18)") (class "Default")
      (node (ref "U3") (pin "18") (pinfunction "BC_EN3_18") (pintype "passive"))
    )
    (net (code "49") (name "unconnected-(U3-NC-Pad8)") (class "Default")
      (node (ref "U3") (pin "8") (pinfunction "NC_8") (pintype "passive"))
    )
    (net (code "50") (name "unconnected-(U3-NC-Pad9)") (class "Default")
      (node (ref "U3") (pin "9") (pinfunction "NC_9") (pintype "passive"))
    )
    (net (code "51") (name "unconnected-(U3-NC-Pad20)") (class "Default")
      (node (ref "U3") (pin "20") (pinfunction "NC_20") (pintype "passive"))
    )
    (net (code "52") (name "unconnected-(U3-NC-Pad21)") (class "Default")
      (node (ref "U3") (pin "21") (pinfunction "NC_21") (pintype "passive"))
    )
    (net (code "53") (name "unconnected-(U3-OCS_N1-Pad13)") (class "Default")
      (node (ref "U3") (pin "13") (pinfunction "OCS_N1_13") (pintype "passive"))
    )
    (net (code "54") (name "unconnected-(U3-OCS_N2-Pad17)") (class "Default")
      (node (ref "U3") (pin "17") (pinfunction "OCS_N2_17") (pintype "passive"))
    )
    (net (code "55") (name "unconnected-(U3-OCS_N3-Pad19)") (class "Default")
      (node (ref "U3") (pin "19") (pinfunction "OCS_N3_19") (pintype "passive"))
    )
    (net (code "56") (name "unconnected-(U3-SUSP_IND-Pad28)") (class "Default")
      (node (ref "U3") (pin "28") (pinfunction "SUSP_IND_28") (pintype "passive"))
    )
    (net (code "57") (name "unconnected-(U3-TEST-Pad11)") (class "Default")
      (node (ref "U3") (pin "11") (pinfunction "TEST_11") (pintype "passive"))
    )
    (net (code "58") (name "unconnected-(U4-FLT_N-PadB2)") (class "Default")
      (node (ref "U4") (pin "B2") (pinfunction "FLT_N_B2") (pintype "passive"))
    )
    (net (code "59") (name "unconnected-(U6-FLT_N-PadB2)") (class "Default")
      (node (ref "U6") (pin "B2") (pinfunction "FLT_N_B2") (pintype "passive"))
    )
    (net (code "60") (name "unconnected-(U16-NR-Pad4)") (class "Default")
      (node (ref "U16") (pin "4") (pinfunction "NR_4") (pintype "passive"))
    )
    (net (code "61") (name "unconnected-(USB1-ID-Pad4)") (class "Default")
      (node (ref "USB1") (pin "4") (pinfunction "ID_4") (pintype "passive"))
    )
    (net (code "62") (name "unconnected-(USB2-ID-Pad4)") (class "Default")
      (node (ref "USB2") (pin "4") (pinfunction "ID_4") (pintype "passive"))
    )
    (net (code "63") (name "unconnected-(USB3-ID-Pad4)") (class "Default")
      (node (ref "USB3") (pin "4") (pinfunction "ID_4") (pintype "passive"))
    )
  )
)
